# mix_txmix.net
KiCad netlist of a schematic drawn in Altium Designer
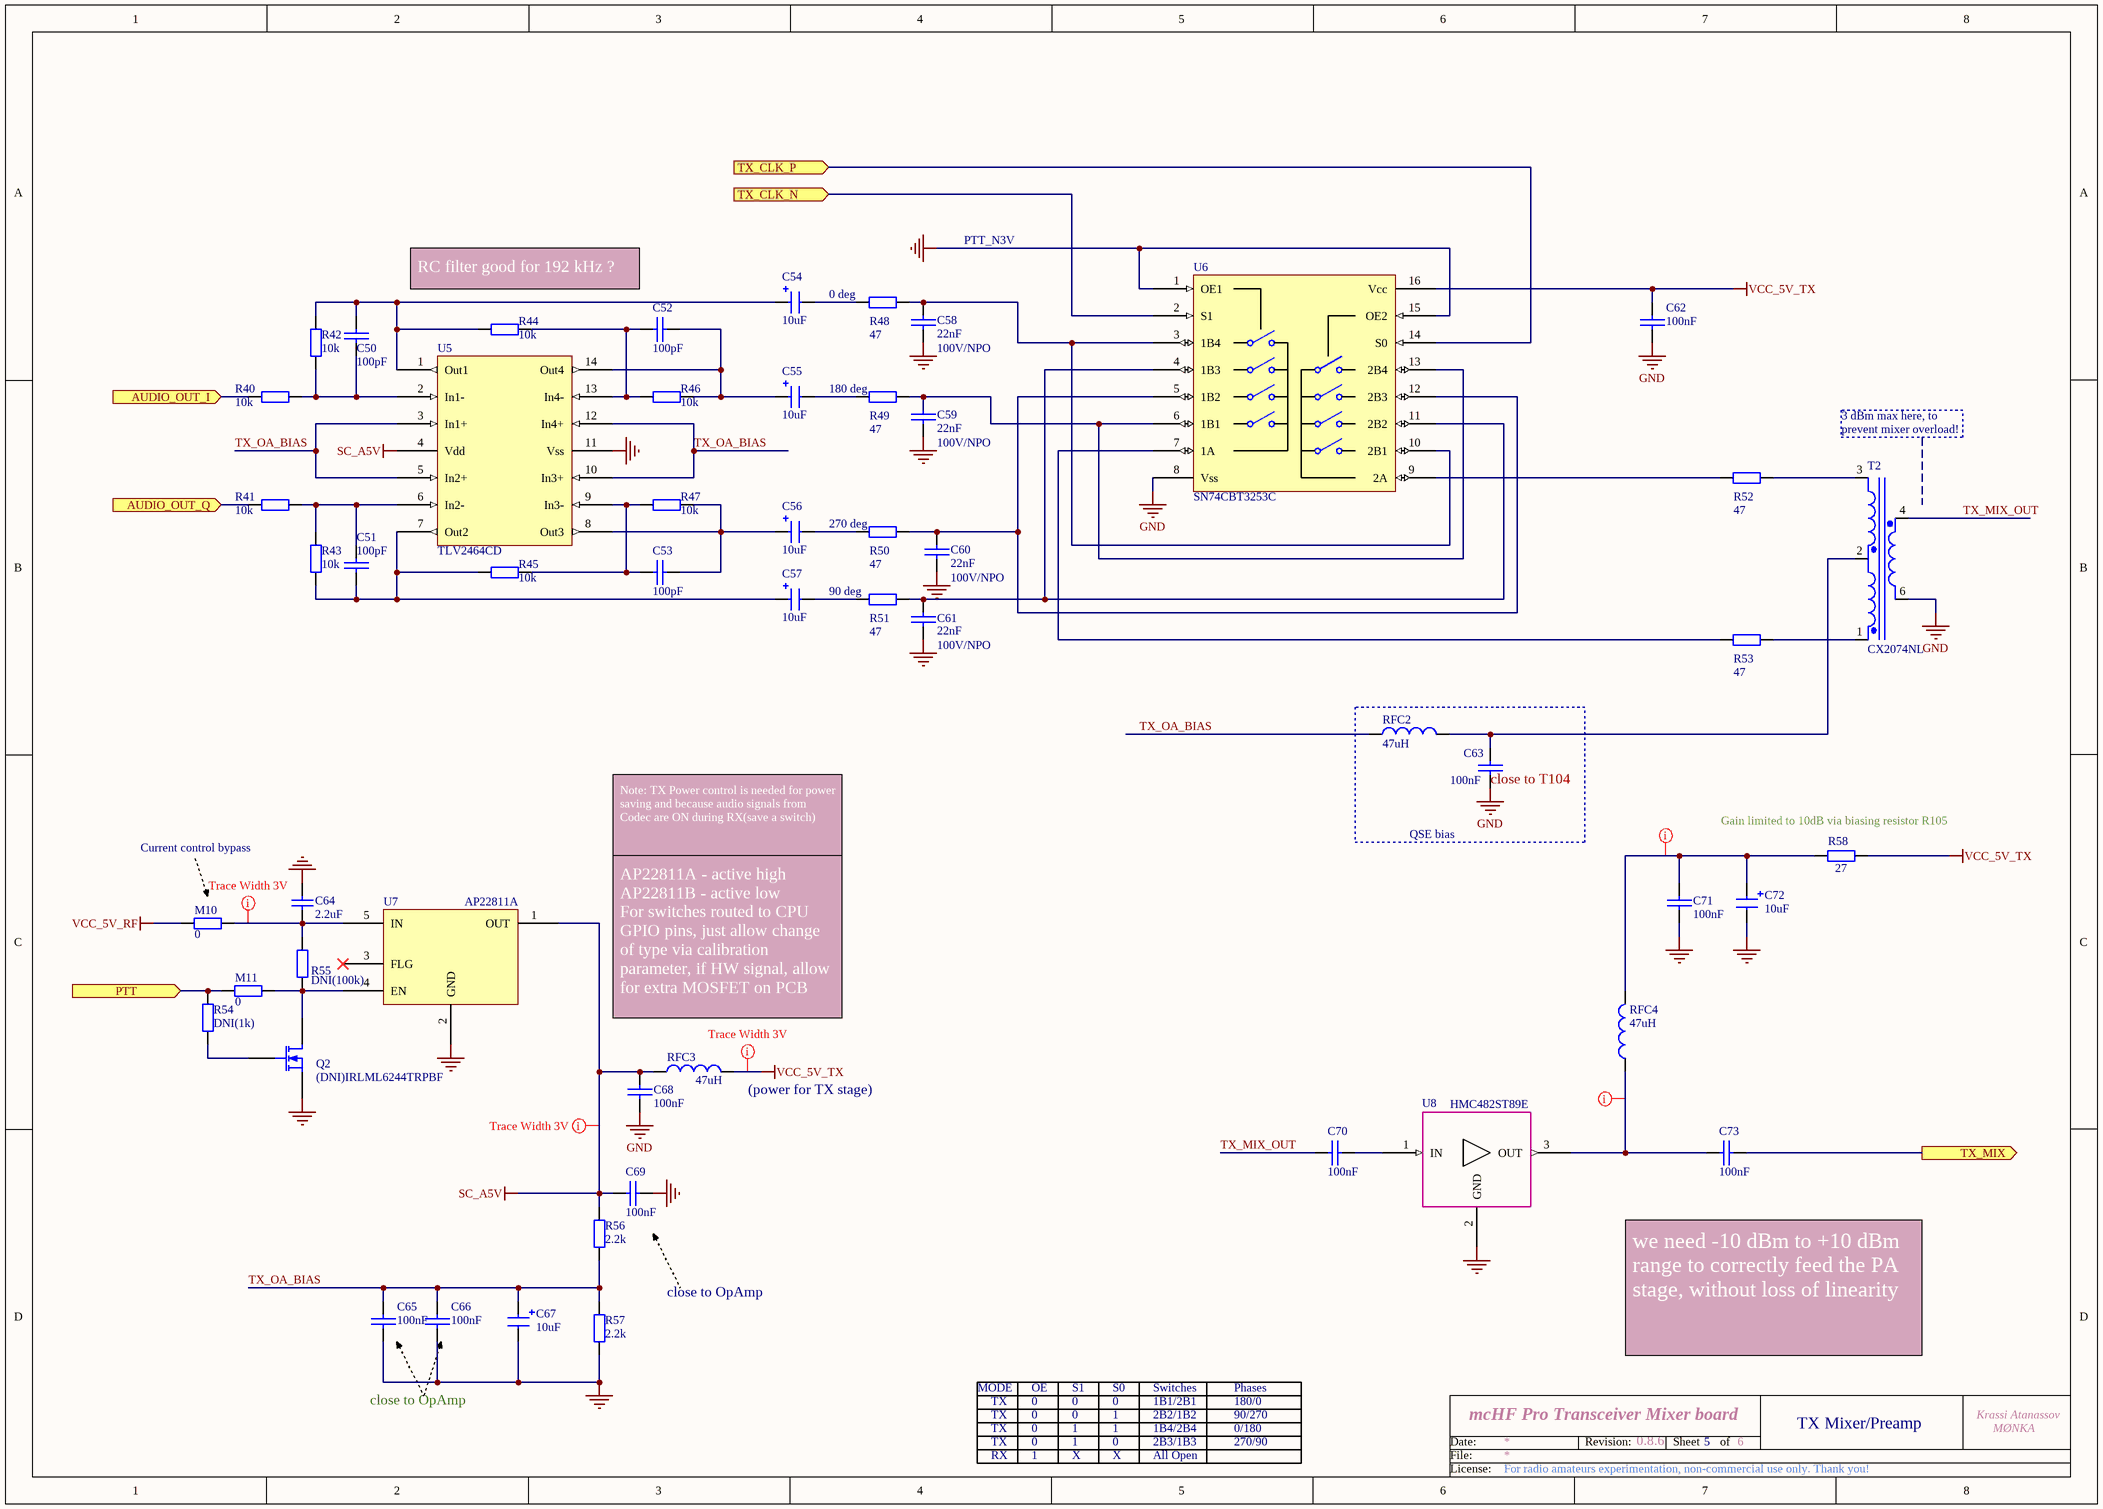
[diagram p0: mix_txmix.SchDoc]

(export (version "E")
  (design (tool "Eeschema 10.0.6"))
  (components
    (comp (ref "C50")
      (value "100pF")
      (footprint "0805")
      (description "Capacitor")
      (libsource (lib "mcHF_rf") (part "CAP"))
    )
    (comp (ref "C51")
      (value "100pF")
      (footprint "0805")
      (description "Capacitor")
      (libsource (lib "mcHF_rf") (part "CAP"))
    )
    (comp (ref "C52")
      (value "100pF")
      (footprint "0805")
      (description "Capacitor")
      (libsource (lib "mcHF_rf") (part "CAP"))
    )
    (comp (ref "C53")
      (value "100pF")
      (footprint "0805")
      (description "Capacitor")
      (libsource (lib "mcHF_rf") (part "CAP"))
    )
    (comp (ref "C54")
      (value "10uF")
      (footprint "1206_Elec_Cap")
      (description "Electrolitic capacitor")
      (libsource (lib "mcHF_rf") (part "CAP-POL"))
    )
    (comp (ref "C55")
      (value "10uF")
      (footprint "1206_Elec_Cap")
      (description "Electrolitic capacitor")
      (libsource (lib "mcHF_rf") (part "CAP-POL"))
    )
    (comp (ref "C56")
      (value "10uF")
      (footprint "1206_Elec_Cap")
      (description "Electrolitic capacitor")
      (libsource (lib "mcHF_rf") (part "CAP-POL"))
    )
    (comp (ref "C57")
      (value "10uF")
      (footprint "1206_Elec_Cap")
      (description "Electrolitic capacitor")
      (libsource (lib "mcHF_rf") (part "CAP-POL"))
    )
    (comp (ref "C58")
      (value "22nF")
      (footprint "CAP_B")
      (description "Capacitor")
      (fields (field (name "VOLTAGE") "100V/NPO"))
      (libsource (lib "mcHF_rf") (part "CAP"))
    )
    (comp (ref "C59")
      (value "22nF")
      (footprint "CAP_B")
      (description "Capacitor")
      (fields (field (name "VOLTAGE") "100V/NPO"))
      (libsource (lib "mcHF_rf") (part "CAP"))
    )
    (comp (ref "C60")
      (value "22nF")
      (footprint "CAP_B")
      (description "Capacitor")
      (fields (field (name "VOLTAGE") "100V/NPO"))
      (libsource (lib "mcHF_rf") (part "CAP"))
    )
    (comp (ref "C61")
      (value "22nF")
      (footprint "CAP_B")
      (description "Capacitor")
      (fields (field (name "VOLTAGE") "100V/NPO"))
      (libsource (lib "mcHF_rf") (part "CAP"))
    )
    (comp (ref "C62")
      (value "100nF")
      (footprint "0805")
      (description "Capacitor")
      (libsource (lib "mcHF_rf") (part "CAP"))
    )
    (comp (ref "C63")
      (value "100nF")
      (footprint "0805")
      (description "Capacitor")
      (libsource (lib "mcHF_rf") (part "CAP"))
    )
    (comp (ref "C64")
      (value "2.2uF")
      (footprint "0805")
      (description "0603  X5R 1礔")
      (fields (field (name "TOLERANCE") "10%"))
      (libsource (lib "MB963_1") (part "CAP SMD 0603  X5R 1礔 25V 10%"))
    )
    (comp (ref "C65")
      (value "100nF")
      (footprint "0805")
      (description "Capacitor")
      (libsource (lib "mcHF_rf") (part "CAP"))
    )
    (comp (ref "C66")
      (value "100nF")
      (footprint "0805")
      (description "Capacitor")
      (libsource (lib "mcHF_rf") (part "CAP"))
    )
    (comp (ref "C67")
      (value "10uF")
      (footprint "1206_Elec_Cap")
      (description "Electrolitic capacitor")
      (libsource (lib "mcHF_rf") (part "CAP-POL"))
    )
    (comp (ref "C68")
      (value "100nF")
      (footprint "0805")
      (description "Capacitor")
      (libsource (lib "mcHF_rf") (part "CAP"))
    )
    (comp (ref "C69")
      (value "100nF")
      (footprint "0805")
      (description "Capacitor")
      (libsource (lib "mcHF_rf") (part "CAP"))
    )
    (comp (ref "C70")
      (value "100nF")
      (footprint "0805")
      (description "Capacitor")
      (libsource (lib "*") (part "CAP"))
    )
    (comp (ref "C71")
      (value "100nF")
      (footprint "0805")
      (description "Capacitor")
      (libsource (lib "*") (part "CAP"))
    )
    (comp (ref "C72")
      (value "10uF")
      (footprint "1206_Elec_Cap")
      (description "Electrolitic capacitor")
      (libsource (lib "mcHF_rf") (part "CAP-POL"))
    )
    (comp (ref "C73")
      (value "100nF")
      (footprint "0805")
      (description "Capacitor")
      (libsource (lib "*") (part "CAP"))
    )
    (comp (ref "M10")
      (value "0")
      (footprint "0805")
      (description "Resistor")
      (libsource (lib "") (part "RES_2"))
    )
    (comp (ref "M11")
      (value "0")
      (footprint "0805")
      (description "Resistor")
      (libsource (lib "mcHF_rf") (part "RES"))
    )
    (comp (ref "Q2")
      (value "(DNI)IRLML6244TRPBF")
      (footprint "SOT-23")
      (description "N-Channel MOSFET")
      (libsource (lib "mcHF_ui_b") (part "MOSFET-N"))
    )
    (comp (ref "R40")
      (value "10k")
      (footprint "0805")
      (description "Resistor")
      (libsource (lib "") (part "RES_2"))
    )
    (comp (ref "R41")
      (value "10k")
      (footprint "0805")
      (description "Resistor")
      (libsource (lib "") (part "RES_2"))
    )
    (comp (ref "R42")
      (value "10k")
      (footprint "0805")
      (description "Resistor")
      (libsource (lib "") (part "RES_1"))
    )
    (comp (ref "R43")
      (value "10k")
      (footprint "0805")
      (description "Resistor")
      (libsource (lib "") (part "RES_1"))
    )
    (comp (ref "R44")
      (value "10k")
      (footprint "0805")
      (description "Resistor")
      (libsource (lib "") (part "RES_2"))
    )
    (comp (ref "R45")
      (value "10k")
      (footprint "0805")
      (description "Resistor")
      (libsource (lib "") (part "RES_2"))
    )
    (comp (ref "R46")
      (value "10k")
      (footprint "0805")
      (description "Resistor")
      (libsource (lib "") (part "RES_2"))
    )
    (comp (ref "R47")
      (value "10k")
      (footprint "0805")
      (description "Resistor")
      (libsource (lib "") (part "RES_2"))
    )
    (comp (ref "R48")
      (value "47")
      (footprint "0805")
      (description "Resistor")
      (libsource (lib "") (part "RES_2"))
    )
    (comp (ref "R49")
      (value "47")
      (footprint "0805")
      (description "Resistor")
      (libsource (lib "") (part "RES_2"))
    )
    (comp (ref "R50")
      (value "47")
      (footprint "0805")
      (description "Resistor")
      (libsource (lib "") (part "RES_2"))
    )
    (comp (ref "R51")
      (value "47")
      (footprint "0805")
      (description "Resistor")
      (libsource (lib "") (part "RES_2"))
    )
    (comp (ref "R52")
      (value "47")
      (footprint "0805")
      (description "Resistor")
      (libsource (lib "") (part "RES_2"))
    )
    (comp (ref "R53")
      (value "47")
      (footprint "0805")
      (description "Resistor")
      (libsource (lib "") (part "RES_2"))
    )
    (comp (ref "R54")
      (value "DNI(1k)")
      (footprint "0805")
      (description "Resistor")
      (libsource (lib "") (part "RES_1"))
    )
    (comp (ref "R55")
      (value "DNI(100k)")
      (footprint "0805")
      (description "Resistor")
      (libsource (lib "mcHF_ui") (part "RES"))
    )
    (comp (ref "R56")
      (value "2.2k")
      (footprint "0805")
      (description "Resistor")
      (libsource (lib "") (part "RES_1"))
    )
    (comp (ref "R57")
      (value "2.2k")
      (footprint "0805")
      (description "Resistor")
      (libsource (lib "") (part "RES_1"))
    )
    (comp (ref "R58")
      (value "27")
      (footprint "1206")
      (description "Resistor")
      (libsource (lib "mcHF_rf") (part "RES"))
    )
    (comp (ref "RFC2")
      (value "47uH")
      (footprint "0805")
      (description "INDUCTOR, SIGNAL LINE, 4.7UH, 1005")
      (libsource (lib "mcHF_rf") (part "TDK-NLV25T"))
    )
    (comp (ref "RFC3")
      (value "47uH")
      (footprint "0805")
      (description "INDUCTOR, SIGNAL LINE, 4.7UH, 1005")
      (libsource (lib "mcHF_rf") (part "TDK-NLV25T"))
    )
    (comp (ref "RFC4")
      (value "47uH")
      (footprint "0805")
      (description "INDUCTOR, SIGNAL LINE, 4.7UH, 1005")
      (libsource (lib "mcHF_rf") (part "TDK-NLV25T"))
    )
    (comp (ref "T2")
      (value "CX2074NL")
      (footprint "SOP5_NEW1")
      (description "Wideband RF Transformer 1:4")
      (libsource (lib "mcHF_rf") (part "CX2074NL"))
    )
    (comp (ref "U5")
      (value "TLV2464CD")
      (footprint "SO-14-Pro")
      (description "Low Power, Rail-To-Rail OpAmp")
      (libsource (lib "mcHF_rf") (part "TLV2464CD"))
    )
    (comp (ref "U6")
      (value "SN74CBT3253C")
      (footprint "SO-16-Pro")
      (description "Dual 4:1 Demux/Analog Switch")
      (libsource (lib "mcHF_rf") (part "SN74CBT3253C"))
    )
    (comp (ref "U7")
      (value "AP22811A")
      (footprint "SOT25-5")
      (description "High-side switch")
      (libsource (lib "__ui") (part "AP22811"))
    )
    (comp (ref "U8")
      (value "HMC482ST89E")
      (footprint "SOT89L_new")
      (description "MMIC AMPLIFIER")
      (libsource (lib "mcHF_rf") (part "HMS482ST89E"))
    )
  )
  (nets
    (net (code "1") (name "/AUDIO_OUT_I") (class "Default")
      (node (ref "R40") (pin "1") (pinfunction "1_1") (pintype "passive"))
    )
    (net (code "2") (name "/AUDIO_OUT_Q") (class "Default")
      (node (ref "R41") (pin "1") (pinfunction "1_1") (pintype "passive"))
    )
    (net (code "3") (name "/PTT") (class "Default")
      (node (ref "M11") (pin "2") (pinfunction "2_2") (pintype "passive"))
      (node (ref "R54") (pin "2") (pinfunction "2_2") (pintype "passive"))
    )
    (net (code "4") (name "/TX_CLK_N") (class "Default")
      (node (ref "U6") (pin "2") (pinfunction "S1_2") (pintype "input"))
    )
    (net (code "5") (name "/TX_CLK_P") (class "Default")
      (node (ref "U6") (pin "14") (pinfunction "S0_14") (pintype "input"))
    )
    (net (code "6") (name "/TX_MIX") (class "Default")
      (node (ref "C73") (pin "1") (pinfunction "1_1") (pintype "passive"))
    )
    (net (code "7") (name "/TX_MIX_OUT") (class "Default")
      (node (ref "C70") (pin "2") (pinfunction "2_2") (pintype "passive"))
      (node (ref "T2") (pin "4") (pinfunction "Pri-_4") (pintype "passive"))
    )
    (net (code "8") (name "/TX_OA_BIAS") (class "Default")
      (node (ref "C65") (pin "2") (pinfunction "2_2") (pintype "passive"))
      (node (ref "C66") (pin "2") (pinfunction "2_2") (pintype "passive"))
      (node (ref "C67") (pin "1") (pinfunction "1_1") (pintype "passive"))
      (node (ref "R56") (pin "1") (pinfunction "1_1") (pintype "passive"))
      (node (ref "R57") (pin "2") (pinfunction "2_2") (pintype "passive"))
      (node (ref "RFC2") (pin "1") (pinfunction "1_1") (pintype "passive"))
      (node (ref "U5") (pin "10") (pinfunction "In3+_10") (pintype "input"))
      (node (ref "U5") (pin "12") (pinfunction "In4+_12") (pintype "input"))
      (node (ref "U5") (pin "3") (pinfunction "In1+_3") (pintype "input"))
      (node (ref "U5") (pin "5") (pinfunction "In2+_5") (pintype "input"))
    )
    (net (code "9") (name "GND") (class "Default")
      (node (ref "C58") (pin "2") (pinfunction "2_2") (pintype "passive"))
      (node (ref "C59") (pin "2") (pinfunction "2_2") (pintype "passive"))
      (node (ref "C60") (pin "2") (pinfunction "2_2") (pintype "passive"))
      (node (ref "C61") (pin "2") (pinfunction "2_2") (pintype "passive"))
      (node (ref "C62") (pin "1") (pinfunction "1_1") (pintype "passive"))
      (node (ref "C63") (pin "1") (pinfunction "1_1") (pintype "passive"))
      (node (ref "C64") (pin "1") (pinfunction "1_1") (pintype "passive"))
      (node (ref "C65") (pin "1") (pinfunction "1_1") (pintype "passive"))
      (node (ref "C66") (pin "1") (pinfunction "1_1") (pintype "passive"))
      (node (ref "C67") (pin "2") (pinfunction "2_2") (pintype "passive"))
      (node (ref "C68") (pin "1") (pinfunction "1_1") (pintype "passive"))
      (node (ref "C69") (pin "1") (pinfunction "1_1") (pintype "passive"))
      (node (ref "C71") (pin "2") (pinfunction "2_2") (pintype "passive"))
      (node (ref "C72") (pin "2") (pinfunction "2_2") (pintype "passive"))
      (node (ref "Q2") (pin "2") (pinfunction "S_2") (pintype "passive"))
      (node (ref "R57") (pin "1") (pinfunction "1_1") (pintype "passive"))
      (node (ref "T2") (pin "6") (pinfunction "Pri+_6") (pintype "passive"))
      (node (ref "U5") (pin "11") (pinfunction "Vss_11") (pintype "power_in"))
      (node (ref "U6") (pin "1") (pinfunction "OE1_1") (pintype "input"))
      (node (ref "U6") (pin "15") (pinfunction "OE2_15") (pintype "input"))
      (node (ref "U6") (pin "8") (pinfunction "Vss_8") (pintype "power_in"))
      (node (ref "U7") (pin "2") (pinfunction "GND_2") (pintype "passive"))
      (node (ref "U8") (pin "2") (pinfunction "GND_2") (pintype "power_in"))
    )
    (net (code "10") (name "Net-(C54-Pad2)") (class "Default")
      (node (ref "C54") (pin "2") (pinfunction "2_2") (pintype "passive"))
      (node (ref "R48") (pin "1") (pinfunction "1_1") (pintype "passive"))
    )
    (net (code "11") (name "Net-(C55-Pad2)") (class "Default")
      (node (ref "C55") (pin "2") (pinfunction "2_2") (pintype "passive"))
      (node (ref "R49") (pin "1") (pinfunction "1_1") (pintype "passive"))
    )
    (net (code "12") (name "Net-(C56-Pad2)") (class "Default")
      (node (ref "C56") (pin "2") (pinfunction "2_2") (pintype "passive"))
      (node (ref "R50") (pin "1") (pinfunction "1_1") (pintype "passive"))
    )
    (net (code "13") (name "Net-(C57-Pad2)") (class "Default")
      (node (ref "C57") (pin "2") (pinfunction "2_2") (pintype "passive"))
      (node (ref "R51") (pin "1") (pinfunction "1_1") (pintype "passive"))
    )
    (net (code "14") (name "Net-(C71-Pad1)") (class "Default")
      (node (ref "C71") (pin "1") (pinfunction "1_1") (pintype "passive"))
      (node (ref "C72") (pin "1") (pinfunction "1_1") (pintype "passive"))
      (node (ref "R58") (pin "2") (pinfunction "2_2") (pintype "passive"))
      (node (ref "RFC4") (pin "2") (pinfunction "2_2") (pintype "passive"))
    )
    (net (code "15") (name "Net-(Q2-D)") (class "Default")
      (node (ref "M11") (pin "1") (pinfunction "1_1") (pintype "passive"))
      (node (ref "Q2") (pin "3") (pinfunction "D_3") (pintype "passive"))
      (node (ref "R55") (pin "2") (pinfunction "2_2") (pintype "passive"))
      (node (ref "U7") (pin "4") (pinfunction "EN_4") (pintype "passive"))
    )
    (net (code "16") (name "Net-(Q2-G)") (class "Default")
      (node (ref "Q2") (pin "1") (pinfunction "G_1") (pintype "passive"))
      (node (ref "R54") (pin "1") (pinfunction "1_1") (pintype "passive"))
    )
    (net (code "17") (name "Net-(T2-Sec0)") (class "Default")
      (node (ref "R53") (pin "2") (pinfunction "2_2") (pintype "passive"))
      (node (ref "T2") (pin "1") (pinfunction "Sec0_1") (pintype "passive"))
    )
    (net (code "18") (name "Net-(T2-Sec180)") (class "Default")
      (node (ref "R52") (pin "2") (pinfunction "2_2") (pintype "passive"))
      (node (ref "T2") (pin "3") (pinfunction "Sec180_3") (pintype "passive"))
    )
    (net (code "19") (name "Net-(T2-SecCmn)") (class "Default")
      (node (ref "C63") (pin "2") (pinfunction "2_2") (pintype "passive"))
      (node (ref "RFC2") (pin "2") (pinfunction "2_2") (pintype "passive"))
      (node (ref "T2") (pin "2") (pinfunction "SecCmn_2") (pintype "passive"))
    )
    (net (code "20") (name "Net-(U5-In1-)") (class "Default")
      (node (ref "C50") (pin "1") (pinfunction "1_1") (pintype "passive"))
      (node (ref "R40") (pin "2") (pinfunction "2_2") (pintype "passive"))
      (node (ref "R42") (pin "1") (pinfunction "1_1") (pintype "passive"))
      (node (ref "U5") (pin "2") (pinfunction "In1-_2") (pintype "input"))
    )
    (net (code "21") (name "Net-(U5-In2-)") (class "Default")
      (node (ref "C51") (pin "2") (pinfunction "2_2") (pintype "passive"))
      (node (ref "R41") (pin "2") (pinfunction "2_2") (pintype "passive"))
      (node (ref "R43") (pin "2") (pinfunction "2_2") (pintype "passive"))
      (node (ref "U5") (pin "6") (pinfunction "In2-_6") (pintype "input"))
    )
    (net (code "22") (name "Net-(U5-In3-)") (class "Default")
      (node (ref "C53") (pin "2") (pinfunction "2_2") (pintype "passive"))
      (node (ref "R45") (pin "2") (pinfunction "2_2") (pintype "passive"))
      (node (ref "R47") (pin "1") (pinfunction "1_1") (pintype "passive"))
      (node (ref "U5") (pin "9") (pinfunction "In3-_9") (pintype "input"))
    )
    (net (code "23") (name "Net-(U5-In4-)") (class "Default")
      (node (ref "C52") (pin "2") (pinfunction "2_2") (pintype "passive"))
      (node (ref "R44") (pin "2") (pinfunction "2_2") (pintype "passive"))
      (node (ref "R46") (pin "1") (pinfunction "1_1") (pintype "passive"))
      (node (ref "U5") (pin "13") (pinfunction "In4-_13") (pintype "input"))
    )
    (net (code "24") (name "Net-(U5-Out1)") (class "Default")
      (node (ref "C50") (pin "2") (pinfunction "2_2") (pintype "passive"))
      (node (ref "C54") (pin "1") (pinfunction "1_1") (pintype "passive"))
      (node (ref "R42") (pin "2") (pinfunction "2_2") (pintype "passive"))
      (node (ref "R44") (pin "1") (pinfunction "1_1") (pintype "passive"))
      (node (ref "U5") (pin "1") (pinfunction "Out1_1") (pintype "output"))
    )
    (net (code "25") (name "Net-(U5-Out2)") (class "Default")
      (node (ref "C51") (pin "1") (pinfunction "1_1") (pintype "passive"))
      (node (ref "C57") (pin "1") (pinfunction "1_1") (pintype "passive"))
      (node (ref "R43") (pin "1") (pinfunction "1_1") (pintype "passive"))
      (node (ref "R45") (pin "1") (pinfunction "1_1") (pintype "passive"))
      (node (ref "U5") (pin "7") (pinfunction "Out2_7") (pintype "output"))
    )
    (net (code "26") (name "Net-(U5-Out3)") (class "Default")
      (node (ref "C53") (pin "1") (pinfunction "1_1") (pintype "passive"))
      (node (ref "C56") (pin "1") (pinfunction "1_1") (pintype "passive"))
      (node (ref "R47") (pin "2") (pinfunction "2_2") (pintype "passive"))
      (node (ref "U5") (pin "8") (pinfunction "Out3_8") (pintype "output"))
    )
    (net (code "27") (name "Net-(U5-Out4)") (class "Default")
      (node (ref "C52") (pin "1") (pinfunction "1_1") (pintype "passive"))
      (node (ref "C55") (pin "1") (pinfunction "1_1") (pintype "passive"))
      (node (ref "R46") (pin "2") (pinfunction "2_2") (pintype "passive"))
      (node (ref "U5") (pin "14") (pinfunction "Out4_14") (pintype "output"))
    )
    (net (code "28") (name "Net-(U6-1A)") (class "Default")
      (node (ref "R53") (pin "1") (pinfunction "1_1") (pintype "passive"))
      (node (ref "U6") (pin "7") (pinfunction "1A_7") (pintype "bidirectional"))
    )
    (net (code "29") (name "Net-(U6-1B1)") (class "Default")
      (node (ref "C59") (pin "1") (pinfunction "1_1") (pintype "passive"))
      (node (ref "R49") (pin "2") (pinfunction "2_2") (pintype "passive"))
      (node (ref "U6") (pin "13") (pinfunction "2B4_13") (pintype "bidirectional"))
      (node (ref "U6") (pin "6") (pinfunction "1B1_6") (pintype "bidirectional"))
    )
    (net (code "30") (name "Net-(U6-1B2)") (class "Default")
      (node (ref "C60") (pin "1") (pinfunction "1_1") (pintype "passive"))
      (node (ref "R50") (pin "2") (pinfunction "2_2") (pintype "passive"))
      (node (ref "U6") (pin "12") (pinfunction "2B3_12") (pintype "bidirectional"))
      (node (ref "U6") (pin "5") (pinfunction "1B2_5") (pintype "bidirectional"))
    )
    (net (code "31") (name "Net-(U6-1B3)") (class "Default")
      (node (ref "C61") (pin "1") (pinfunction "1_1") (pintype "passive"))
      (node (ref "R51") (pin "2") (pinfunction "2_2") (pintype "passive"))
      (node (ref "U6") (pin "11") (pinfunction "2B2_11") (pintype "bidirectional"))
      (node (ref "U6") (pin "4") (pinfunction "1B3_4") (pintype "bidirectional"))
    )
    (net (code "32") (name "Net-(U6-1B4)") (class "Default")
      (node (ref "C58") (pin "1") (pinfunction "1_1") (pintype "passive"))
      (node (ref "R48") (pin "2") (pinfunction "2_2") (pintype "passive"))
      (node (ref "U6") (pin "10") (pinfunction "2B1_10") (pintype "bidirectional"))
      (node (ref "U6") (pin "3") (pinfunction "1B4_3") (pintype "bidirectional"))
    )
    (net (code "33") (name "Net-(U6-2A)") (class "Default")
      (node (ref "R52") (pin "1") (pinfunction "1_1") (pintype "passive"))
      (node (ref "U6") (pin "9") (pinfunction "2A_9") (pintype "bidirectional"))
    )
    (net (code "34") (name "Net-(U7-IN)") (class "Default")
      (node (ref "C64") (pin "2") (pinfunction "2_2") (pintype "passive"))
      (node (ref "M10") (pin "2") (pinfunction "2_2") (pintype "passive"))
      (node (ref "R55") (pin "1") (pinfunction "1_1") (pintype "passive"))
      (node (ref "U7") (pin "5") (pinfunction "IN_5") (pintype "power_in"))
    )
    (net (code "35") (name "Net-(U8-IN)") (class "Default")
      (node (ref "C70") (pin "1") (pinfunction "1_1") (pintype "passive"))
      (node (ref "U8") (pin "1") (pinfunction "IN_1") (pintype "input"))
    )
    (net (code "36") (name "Net-(U8-OUT)") (class "Default")
      (node (ref "C73") (pin "2") (pinfunction "2_2") (pintype "passive"))
      (node (ref "RFC4") (pin "1") (pinfunction "1_1") (pintype "passive"))
      (node (ref "U8") (pin "3") (pinfunction "OUT_3") (pintype "output"))
    )
    (net (code "37") (name "SC_A5V") (class "Default")
      (node (ref "C68") (pin "2") (pinfunction "2_2") (pintype "passive"))
      (node (ref "C69") (pin "2") (pinfunction "2_2") (pintype "passive"))
      (node (ref "R56") (pin "2") (pinfunction "2_2") (pintype "passive"))
      (node (ref "RFC3") (pin "1") (pinfunction "1_1") (pintype "passive"))
      (node (ref "U5") (pin "4") (pinfunction "Vdd_4") (pintype "power_in"))
      (node (ref "U7") (pin "1") (pinfunction "OUT_1") (pintype "power_in"))
    )
    (net (code "38") (name "VCC_5V_RF") (class "Default")
      (node (ref "M10") (pin "1") (pinfunction "1_1") (pintype "passive"))
    )
    (net (code "39") (name "VCC_5V_TX") (class "Default")
      (node (ref "C62") (pin "2") (pinfunction "2_2") (pintype "passive"))
      (node (ref "R58") (pin "1") (pinfunction "1_1") (pintype "passive"))
      (node (ref "RFC3") (pin "2") (pinfunction "2_2") (pintype "passive"))
      (node (ref "U6") (pin "16") (pinfunction "Vcc_16") (pintype "power_in"))
    )
    (net (code "40") (name "unconnected-(U7-FLG-Pad3)") (class "Default")
      (node (ref "U7") (pin "3") (pinfunction "FLG_3") (pintype "passive+no_connect"))
    )
  )
)
